# Copy_of_Power.net
KiCad netlist of a schematic drawn in Altium Designer
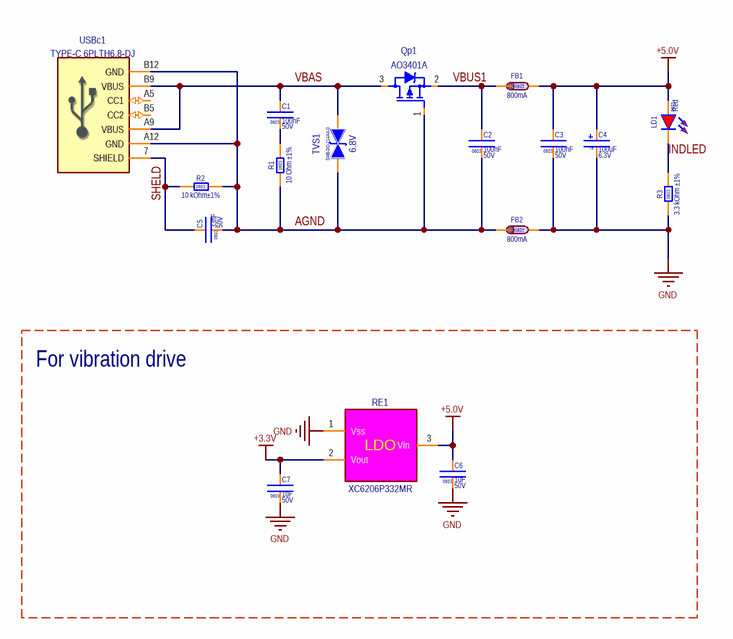
[diagram p0: Copy of Power.SchDoc]

(export (version "E")
  (design (tool "Eeschema 10.0.6"))
  (components
    (comp (ref "C1")
      (value "100nF")
      (footprint "CC0603(1608)x0.8")
      (description "100 nF ±10% 50V X7R")
      (fields
        (field (name "TOLERANCE") "±10%")
        (field (name "VOLTAGE") "50V")
        (field (name "Comment") "100 nF ±10% 50V")
        (field (name "PUBLISHER") "Catcatcat Electronics")
      )
      (libsource (lib "IPC-7351chipCAPC") (part "0603 0.1 uF (B)"))
    )
    (comp (ref "C2")
      (value "100nF")
      (footprint "CC0603(1608)x0.8")
      (description "100 nF ±10% 50V X7R")
      (fields
        (field (name "TOLERANCE") "±10%")
        (field (name "VOLTAGE") "50V")
        (field (name "Comment") "100 nF ±10% 50V")
        (field (name "PUBLISHER") "Catcatcat Electronics")
      )
      (libsource (lib "IPC-7351chipCAPC") (part "0603 0.1 uF (B)"))
    )
    (comp (ref "C3")
      (value "100nF")
      (footprint "CC0603(1608)x0.8")
      (description "100 nF ±10% 50V X7R")
      (fields
        (field (name "TOLERANCE") "±10%")
        (field (name "VOLTAGE") "50V")
        (field (name "Comment") "100 nF ±10% 50V")
        (field (name "PUBLISHER") "Catcatcat Electronics")
      )
      (libsource (lib "IPC-7351chipCAPC") (part "0603 0.1 uF (B)"))
    )
    (comp (ref "C4")
      (value "100uF")
      (footprint "TANTAL_B")
      (description "Tantalum Capacitors 100uF 6.3V CASE-B_3528 RoHS")
      (fields
        (field (name "VOLTAGE") "6.3V")
        (field (name "Comment") "100UF 6.3V CASE-B_3528")
        (field (name "PUBLISHER") "Catcatcat Electronics")
      )
      (libsource (lib "CapacitorElectrolytic") (part "TANTAL-B 100uF 6.3V (B)"))
    )
    (comp (ref "C5")
      (value "33nF")
      (footprint "CC0603")
      (description "33 nF ±10% 50V X7R")
      (fields
        (field (name "TOLERANCE") "±10%")
        (field (name "OCTOPART") "https://octopart.com/search?q=CL10B333KB8NNNC&currency=USD&specs=0")
        (field (name "VOLTAGE") "50V")
        (field (name "PUBLISHER") "Catcatcat Electronics")
      )
      (libsource (lib "IPC-7351chipCAPC") (part "0603 0.033 uF (B)"))
    )
    (comp (ref "C6")
      (value "1uF")
      (footprint "CC0603(1608)x0.8")
      (description "1.0 uF ±10% 50V X5R")
      (fields
        (field (name "TOLERANCE") "±10%")
        (field (name "VOLTAGE") "50V")
        (field (name "Comment") "1uF ±10% 50V 0603")
        (field (name "PUBLISHER") "Catcatcat Electronics")
      )
      (libsource (lib "IPC-7351chipCAPC") (part "0603 1.0 uF (B)"))
    )
    (comp (ref "C7")
      (value "1uF")
      (footprint "CC0603(1608)x0.8")
      (description "1.0 uF ±10% 50V X5R")
      (fields
        (field (name "TOLERANCE") "±10%")
        (field (name "VOLTAGE") "50V")
        (field (name "Comment") "1uF ±10% 50V 0603")
        (field (name "PUBLISHER") "Catcatcat Electronics")
      )
      (libsource (lib "IPC-7351chipCAPC") (part "0603 1.0 uF (B)"))
    )
    (comp (ref "FB1")
      (value "800mA")
      (footprint "FB0805(2012)")
      (description "0.80A 100 Ohm @100MHz 150 mOhm")
      (fields (field (name "Comment") "GZ2012D101TF") (field (name "PUBLISHER") "Catcatcat Electronics"))
      (libsource (lib "IPC-7351chipFEB") (part "0805 GZ2012D101TF (B)"))
    )
    (comp (ref "FB2")
      (value "800mA")
      (footprint "FB0805(2012)")
      (description "0.80A 100 Ohm @100MHz 150 mOhm")
      (fields (field (name "Comment") "GZ2012D101TF") (field (name "PUBLISHER") "Catcatcat Electronics"))
      (libsource (lib "IPC-7351chipFEB") (part "0805 GZ2012D101TF (B)"))
    )
    (comp (ref "LD1")
      (value "Red")
      (footprint "LD0603 RED")
      (description "0603 Red 520~625NM 90~100MCD@20MA Top View RoHS")
      (fields
        (field (name "CASE/PACKAGE") "0603")
        (field (name "Comment") "KT-0603R")
        (field (name "PUBLISHER") "Catcatcat Electronics")
      )
      (libsource (lib "Led") (part "KT-0603R (B)"))
    )
    (comp (ref "Qp1")
      (value "AO3401A")
      (footprint "FP-SOT23-IPC_A")
      (description "P-Channel SOT-23-3L 30V 4A 44mΩ@10V,4.3A 1.4W 1.3V@250uAl SOT-23-3L  MOSFETs ROHS")
      (fields (field (name "VOLTAGE") "30V 4A") (field (name "PUBLISHER") "Catcatcat Electronics"))
      (libsource (lib "Transistors") (part "AO3401A (B)"))
    )
    (comp (ref "R1")
      (value "10 Ohm ±1%")
      (footprint "RC0603(1608) -1%")
      (description "10 R (XIO) ±1% 1/10W 50V ±400ppm/°C")
      (fields
        (field (name "TOLERANCE") "±1%")
        (field (name "VOLTAGE") "50V")
        (field (name "PUBLISHER") "Catcatcat Electronics")
      )
      (libsource (lib "IPC-7351chipRESC") (part "0603 10 Ohm ±1% (B)"))
    )
    (comp (ref "R2")
      (value "10 kOhm±1%")
      (footprint "RC0603(1608) -1%")
      (description "10 k (103) ±1% 1/10W")
      (fields
        (field (name "TOLERANCE") "±1%")
        (field (name "VOLTAGE") "50V")
        (field (name "PUBLISHER") "Catcatcat Electronics")
      )
      (libsource (lib "IPC-7351chipRESC") (part "0603 10 kOhm ±1% (B)"))
    )
    (comp (ref "R3")
      (value "3.3 kOhm ±1%")
      (footprint "RC0603(1608) -1%")
      (description "3.3 k (332) ±1% 1/10W 75V")
      (fields
        (field (name "TOLERANCE") "±1%")
        (field (name "VOLTAGE") "75V")
        (field (name "PUBLISHER") "Catcatcat Electronics")
      )
      (libsource (lib "IPC-7351chipRESC") (part "0603 3.3 kOhm ±1% (B)"))
    )
    (comp (ref "RE1")
      (value "XC6206P332MR")
      (footprint "SOT-23-3L")
      (description "LDO 5.0V 3.3V 200mA Fixed 3.3V~3.3V Positive 6V SOT-23-3L  Linear Voltage Regulators (LDO) ROHS")
      (fields (field (name "VOLTAGE") "3.3V") (field (name "PUBLISHER") "Catcatcat Electronics"))
      (libsource (lib "Power") (part "XC6206P332MR (B)"))
    )
    (comp (ref "TVS1")
      (value "6.8V")
      (footprint "SMB/DO-214AA")
      (description "TVS 6.8V SMB(DO-214AA) ROHS")
      (fields
        (field (name "CASE/PACKAGE") "SMB-DO-214AA-0")
        (field (name "Comment") "P6SMB6.8CA")
        (field (name "PUBLISHER") "Catcatcat Electronics")
      )
      (libsource (lib "CircuitProtection") (part "P6SMB6.8CA (B)"))
    )
    (comp (ref "USBc1")
      (value "TYPE-C 6PLTH6.8-DJ")
      (footprint "YTC-TC6-555")
      (description "Type C V USB 2.0 6P 3A Power Connectors ROHS")
      (fields (field (name "VOLTAGE") "20V 3A") (field (name "PUBLISHER") "Catcatcat Electronics"))
      (libsource (lib "Connector_Interface") (part "TYPE-C 6PLTH6.8-DJ (E)"))
    )
  )
  (nets
    (net (code "1") (name "+3.3V") (class "Default")
      (node (ref "C7") (pin "2") (pintype "passive"))
      (node (ref "RE1") (pin "2") (pinfunction "Vout_2") (pintype "passive"))
    )
    (net (code "2") (name "+5.0V") (class "Default")
      (node (ref "C3") (pin "2") (pintype "passive"))
      (node (ref "C4") (pin "1") (pintype "passive"))
      (node (ref "C6") (pin "2") (pintype "passive"))
      (node (ref "FB1") (pin "2") (pintype "passive"))
      (node (ref "LD1") (pin "2") (pintype "passive"))
      (node (ref "RE1") (pin "3") (pinfunction "Vin_3") (pintype "passive"))
    )
    (net (code "3") (name "/AGND") (class "Default")
      (node (ref "C2") (pin "1") (pintype "passive"))
      (node (ref "C5") (pin "1") (pintype "passive"))
      (node (ref "FB2") (pin "1") (pintype "passive"))
      (node (ref "Qp1") (pin "1") (pinfunction "G_1") (pintype "passive"))
      (node (ref "R1") (pin "1") (pintype "passive"))
      (node (ref "R2") (pin "2") (pintype "passive"))
      (node (ref "TVS1") (pin "1") (pintype "passive"))
      (node (ref "USBc1") (pin "A12") (pinfunction "GND_A12") (pintype "passive"))
      (node (ref "USBc1") (pin "B12") (pinfunction "GND_B12") (pintype "passive"))
    )
    (net (code "4") (name "/INDLED") (class "Default")
      (node (ref "LD1") (pin "1") (pintype "passive"))
      (node (ref "R3") (pin "2") (pintype "passive"))
    )
    (net (code "5") (name "/SHELD") (class "Default")
      (node (ref "C5") (pin "2") (pintype "passive"))
      (node (ref "R2") (pin "1") (pintype "passive"))
      (node (ref "USBc1") (pin "7") (pinfunction "SHIELD_7") (pintype "passive"))
    )
    (net (code "6") (name "/VBAS") (class "Default")
      (node (ref "C1") (pin "2") (pintype "passive"))
      (node (ref "Qp1") (pin "3") (pinfunction "D_3") (pintype "passive"))
      (node (ref "TVS1") (pin "2") (pintype "passive"))
      (node (ref "USBc1") (pin "A9") (pinfunction "VBUS_A9") (pintype "passive"))
      (node (ref "USBc1") (pin "B9") (pinfunction "VBUS_B9") (pintype "passive"))
    )
    (net (code "7") (name "/VBUS1") (class "Default")
      (node (ref "C2") (pin "2") (pintype "passive"))
      (node (ref "FB1") (pin "1") (pintype "passive"))
      (node (ref "Qp1") (pin "2") (pinfunction "S_2") (pintype "passive"))
    )
    (net (code "8") (name "GND") (class "Default")
      (node (ref "C3") (pin "1") (pintype "passive"))
      (node (ref "C4") (pin "2") (pintype "passive"))
      (node (ref "C6") (pin "1") (pintype "passive"))
      (node (ref "C7") (pin "1") (pintype "passive"))
      (node (ref "FB2") (pin "2") (pintype "passive"))
      (node (ref "R3") (pin "1") (pintype "passive"))
      (node (ref "RE1") (pin "1") (pinfunction "Vss_1") (pintype "passive"))
    )
    (net (code "9") (name "Net-(C1-Pad1)") (class "Default")
      (node (ref "C1") (pin "1") (pintype "passive"))
      (node (ref "R1") (pin "2") (pintype "passive"))
    )
    (net (code "10") (name "unconnected-(USBc1-CC1-PadA5)") (class "Default")
      (node (ref "USBc1") (pin "A5") (pinfunction "CC1_A5") (pintype "bidirectional"))
    )
    (net (code "11") (name "unconnected-(USBc1-CC2-PadB5)") (class "Default")
      (node (ref "USBc1") (pin "B5") (pinfunction "CC2_B5") (pintype "bidirectional"))
    )
  )
)
